# senror_input.net
KiCad netlist of a schematic drawn in Altium Designer
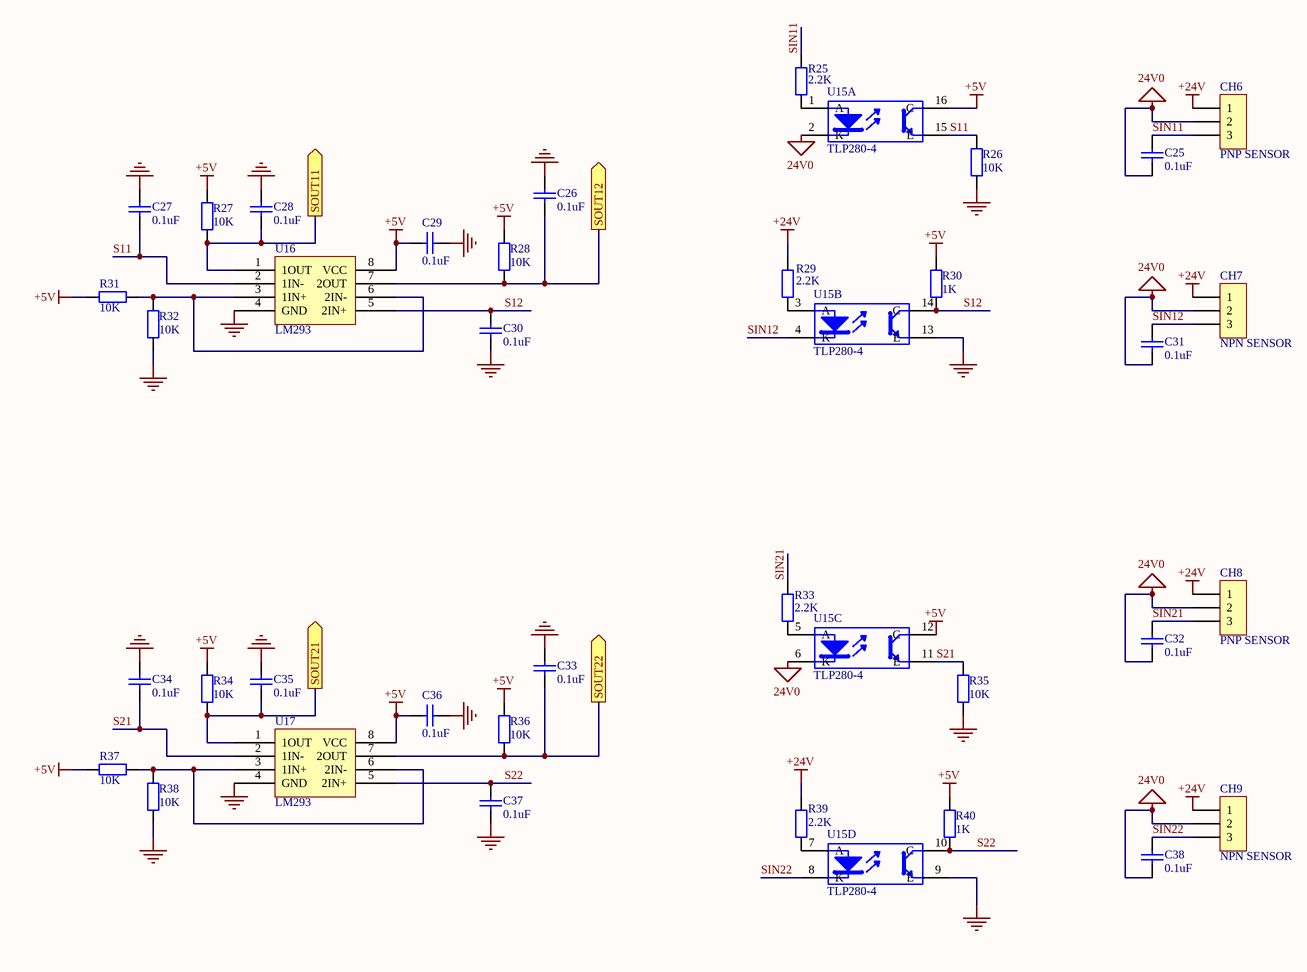
[diagram p0: senror_input.SchDoc]

(export (version "E")
  (design (tool "Eeschema 10.0.6"))
  (components
    (comp (ref "C25")
      (value "0.1uF")
      (footprint "0805")
      (description "Capacitor")
      (fields (field (name "Comment") "Cap") (field (name "PUBLISHER") "Altium Limited"))
      (libsource (lib "Miscellaneous Devices") (part "Cap"))
    )
    (comp (ref "C26")
      (value "0.1uF")
      (footprint "0805")
      (description "Capacitor")
      (fields (field (name "Comment") "Cap") (field (name "PUBLISHER") "Altium Limited"))
      (libsource (lib "Miscellaneous Devices") (part "Cap"))
    )
    (comp (ref "C27")
      (value "0.1uF")
      (footprint "0805")
      (description "Capacitor")
      (fields (field (name "Comment") "Cap") (field (name "PUBLISHER") "Altium Limited"))
      (libsource (lib "Miscellaneous Devices") (part "Cap"))
    )
    (comp (ref "C28")
      (value "0.1uF")
      (footprint "0805")
      (description "Capacitor")
      (fields (field (name "Comment") "Cap") (field (name "PUBLISHER") "Altium Limited"))
      (libsource (lib "Miscellaneous Devices") (part "Cap"))
    )
    (comp (ref "C29")
      (value "0.1uF")
      (footprint "0805")
      (description "Capacitor")
      (fields (field (name "Comment") "Cap") (field (name "PUBLISHER") "Altium Limited"))
      (libsource (lib "Miscellaneous Devices") (part "Cap"))
    )
    (comp (ref "C30")
      (value "0.1uF")
      (footprint "0805")
      (description "Capacitor")
      (fields (field (name "Comment") "Cap") (field (name "PUBLISHER") "Altium Limited"))
      (libsource (lib "Miscellaneous Devices") (part "Cap"))
    )
    (comp (ref "C31")
      (value "0.1uF")
      (footprint "0805")
      (description "Capacitor")
      (fields (field (name "Comment") "Cap") (field (name "PUBLISHER") "Altium Limited"))
      (libsource (lib "Miscellaneous Devices") (part "Cap"))
    )
    (comp (ref "C32")
      (value "0.1uF")
      (footprint "0805")
      (description "Capacitor")
      (fields (field (name "Comment") "Cap") (field (name "PUBLISHER") "Altium Limited"))
      (libsource (lib "Miscellaneous Devices") (part "Cap"))
    )
    (comp (ref "C33")
      (value "0.1uF")
      (footprint "0805")
      (description "Capacitor")
      (fields (field (name "Comment") "Cap") (field (name "PUBLISHER") "Altium Limited"))
      (libsource (lib "Miscellaneous Devices") (part "Cap"))
    )
    (comp (ref "C34")
      (value "0.1uF")
      (footprint "0805")
      (description "Capacitor")
      (fields (field (name "Comment") "Cap") (field (name "PUBLISHER") "Altium Limited"))
      (libsource (lib "Miscellaneous Devices") (part "Cap"))
    )
    (comp (ref "C35")
      (value "0.1uF")
      (footprint "0805")
      (description "Capacitor")
      (fields (field (name "Comment") "Cap") (field (name "PUBLISHER") "Altium Limited"))
      (libsource (lib "Miscellaneous Devices") (part "Cap"))
    )
    (comp (ref "C36")
      (value "0.1uF")
      (footprint "0805")
      (description "Capacitor")
      (fields (field (name "Comment") "Cap") (field (name "PUBLISHER") "Altium Limited"))
      (libsource (lib "Miscellaneous Devices") (part "Cap"))
    )
    (comp (ref "C37")
      (value "0.1uF")
      (footprint "0805")
      (description "Capacitor")
      (fields (field (name "Comment") "Cap") (field (name "PUBLISHER") "Altium Limited"))
      (libsource (lib "Miscellaneous Devices") (part "Cap"))
    )
    (comp (ref "C38")
      (value "0.1uF")
      (footprint "0805")
      (description "Capacitor")
      (fields (field (name "Comment") "Cap") (field (name "PUBLISHER") "Altium Limited"))
      (libsource (lib "Miscellaneous Devices") (part "Cap"))
    )
    (comp (ref "CH6")
      (value "HEADER1X3")
      (footprint "CH3.96-3PIN")
      (fields (field (name "ALTIUM_UNNAMED_1") "PNP SENSOR"))
      (libsource (lib "myIntegrated_Library1") (part "HEADER1X3"))
    )
    (comp (ref "CH7")
      (value "HEADER1X3")
      (footprint "CH3.96-3PIN")
      (fields (field (name "ALTIUM_UNNAMED_1") "NPN SENSOR"))
      (libsource (lib "myIntegrated_Library1") (part "HEADER1X3"))
    )
    (comp (ref "CH8")
      (value "HEADER1X3")
      (footprint "CH3.96-3PIN")
      (fields (field (name "ALTIUM_UNNAMED_1") "PNP SENSOR"))
      (libsource (lib "myIntegrated_Library1") (part "HEADER1X3"))
    )
    (comp (ref "CH9")
      (value "HEADER1X3")
      (footprint "CH3.96-3PIN")
      (fields (field (name "ALTIUM_UNNAMED_1") "NPN SENSOR"))
      (libsource (lib "myIntegrated_Library1") (part "HEADER1X3"))
    )
    (comp (ref "R25")
      (value "2.2K")
      (footprint "0805")
      (description "Resistor")
      (fields (field (name "Comment") "Res2") (field (name "PUBLISHER") "Altium Limited"))
      (libsource (lib "Miscellaneous Devices") (part "Res2"))
    )
    (comp (ref "R26")
      (value "10K")
      (footprint "0805")
      (description "Resistor")
      (fields (field (name "Comment") "Res2") (field (name "PUBLISHER") "Altium Limited"))
      (libsource (lib "Miscellaneous Devices") (part "Res2"))
    )
    (comp (ref "R27")
      (value "10K")
      (footprint "0805")
      (description "Resistor")
      (fields (field (name "Comment") "Res2") (field (name "PUBLISHER") "Altium Limited"))
      (libsource (lib "Miscellaneous Devices") (part "Res2"))
    )
    (comp (ref "R28")
      (value "10K")
      (footprint "0805")
      (description "Resistor")
      (fields (field (name "Comment") "Res2") (field (name "PUBLISHER") "Altium Limited"))
      (libsource (lib "Miscellaneous Devices") (part "Res2"))
    )
    (comp (ref "R29")
      (value "2.2K")
      (footprint "0805")
      (description "Resistor")
      (fields (field (name "Comment") "Res2") (field (name "PUBLISHER") "Altium Limited"))
      (libsource (lib "Miscellaneous Devices") (part "Res2"))
    )
    (comp (ref "R30")
      (value "1K")
      (footprint "0805")
      (description "Resistor")
      (fields (field (name "Comment") "Res2") (field (name "PUBLISHER") "Altium Limited"))
      (libsource (lib "Miscellaneous Devices") (part "Res2"))
    )
    (comp (ref "R31")
      (value "10K")
      (footprint "0805")
      (description "Resistor")
      (fields (field (name "Comment") "Res2") (field (name "PUBLISHER") "Altium Limited"))
      (libsource (lib "") (part "Res2_1"))
    )
    (comp (ref "R32")
      (value "10K")
      (footprint "0805")
      (description "Resistor")
      (fields (field (name "Comment") "Res2") (field (name "PUBLISHER") "Altium Limited"))
      (libsource (lib "Miscellaneous Devices") (part "Res2"))
    )
    (comp (ref "R33")
      (value "2.2K")
      (footprint "0805")
      (description "Resistor")
      (fields (field (name "Comment") "Res2") (field (name "PUBLISHER") "Altium Limited"))
      (libsource (lib "Miscellaneous Devices") (part "Res2"))
    )
    (comp (ref "R34")
      (value "10K")
      (footprint "0805")
      (description "Resistor")
      (fields (field (name "Comment") "Res2") (field (name "PUBLISHER") "Altium Limited"))
      (libsource (lib "Miscellaneous Devices") (part "Res2"))
    )
    (comp (ref "R35")
      (value "10K")
      (footprint "0805")
      (description "Resistor")
      (fields (field (name "Comment") "Res2") (field (name "PUBLISHER") "Altium Limited"))
      (libsource (lib "Miscellaneous Devices") (part "Res2"))
    )
    (comp (ref "R36")
      (value "10K")
      (footprint "0805")
      (description "Resistor")
      (fields (field (name "Comment") "Res2") (field (name "PUBLISHER") "Altium Limited"))
      (libsource (lib "Miscellaneous Devices") (part "Res2"))
    )
    (comp (ref "R37")
      (value "10K")
      (footprint "0805")
      (description "Resistor")
      (fields (field (name "Comment") "Res2") (field (name "PUBLISHER") "Altium Limited"))
      (libsource (lib "") (part "Res2_1"))
    )
    (comp (ref "R38")
      (value "10K")
      (footprint "0805")
      (description "Resistor")
      (fields (field (name "Comment") "Res2") (field (name "PUBLISHER") "Altium Limited"))
      (libsource (lib "Miscellaneous Devices") (part "Res2"))
    )
    (comp (ref "R39")
      (value "2.2K")
      (footprint "0805")
      (description "Resistor")
      (fields (field (name "Comment") "Res2") (field (name "PUBLISHER") "Altium Limited"))
      (libsource (lib "Miscellaneous Devices") (part "Res2"))
    )
    (comp (ref "R40")
      (value "1K")
      (footprint "0805")
      (description "Resistor")
      (fields (field (name "Comment") "Res2") (field (name "PUBLISHER") "Altium Limited"))
      (libsource (lib "Miscellaneous Devices") (part "Res2"))
    )
    (comp (ref "U15") (value "TLP280-4") (footprint "SO16") (libsource (lib "WH V20") (part "TLP521-4")))
    (comp (ref "U16")
      (value "LM293")
      (footprint "SOP8-OP27")
      (libsource (lib "myIntegrated_Library1") (part "LM293"))
    )
    (comp (ref "U17")
      (value "LM293")
      (footprint "SOP8-OP27")
      (libsource (lib "myIntegrated_Library1") (part "LM293"))
    )
  )
  (nets
    (net (code "1") (name "+5V") (class "Default")
      (node (ref "C29") (pin "2") (pinfunction "2_2") (pintype "passive"))
      (node (ref "C36") (pin "2") (pinfunction "2_2") (pintype "passive"))
      (node (ref "R27") (pin "1") (pinfunction "1_1") (pintype "passive"))
      (node (ref "R28") (pin "1") (pinfunction "1_1") (pintype "passive"))
      (node (ref "R30") (pin "1") (pinfunction "1_1") (pintype "passive"))
      (node (ref "R31") (pin "1") (pinfunction "1_1") (pintype "passive"))
      (node (ref "R34") (pin "1") (pinfunction "1_1") (pintype "passive"))
      (node (ref "R36") (pin "1") (pinfunction "1_1") (pintype "passive"))
      (node (ref "R37") (pin "1") (pinfunction "1_1") (pintype "passive"))
      (node (ref "R40") (pin "1") (pinfunction "1_1") (pintype "passive"))
      (node (ref "U15") (pin "12") (pinfunction "C_12") (pintype "passive"))
      (node (ref "U15") (pin "16") (pinfunction "C_16") (pintype "passive"))
      (node (ref "U16") (pin "8") (pinfunction "VCC_8") (pintype "passive"))
      (node (ref "U17") (pin "8") (pinfunction "VCC_8") (pintype "passive"))
    )
    (net (code "2") (name "+24V") (class "Default")
      (node (ref "CH6") (pin "1") (pinfunction "1_1") (pintype "passive"))
      (node (ref "CH7") (pin "1") (pinfunction "1_1") (pintype "passive"))
      (node (ref "CH8") (pin "1") (pinfunction "1_1") (pintype "passive"))
      (node (ref "CH9") (pin "1") (pinfunction "1_1") (pintype "passive"))
      (node (ref "R29") (pin "1") (pinfunction "1_1") (pintype "passive"))
      (node (ref "R39") (pin "1") (pinfunction "1_1") (pintype "passive"))
    )
    (net (code "3") (name "/S11") (class "Default")
      (node (ref "C27") (pin "2") (pinfunction "2_2") (pintype "passive"))
      (node (ref "R26") (pin "1") (pinfunction "1_1") (pintype "passive"))
      (node (ref "U15") (pin "15") (pinfunction "E_15") (pintype "passive"))
      (node (ref "U16") (pin "2") (pinfunction "1IN-_2") (pintype "passive"))
    )
    (net (code "4") (name "/S12") (class "Default")
      (node (ref "C30") (pin "2") (pinfunction "2_2") (pintype "passive"))
      (node (ref "R30") (pin "2") (pinfunction "2_2") (pintype "passive"))
      (node (ref "U15") (pin "14") (pinfunction "C_14") (pintype "passive"))
      (node (ref "U16") (pin "5") (pinfunction "2IN+_5") (pintype "passive"))
    )
    (net (code "5") (name "/S21") (class "Default")
      (node (ref "C34") (pin "2") (pinfunction "2_2") (pintype "passive"))
      (node (ref "R35") (pin "1") (pinfunction "1_1") (pintype "passive"))
      (node (ref "U15") (pin "11") (pinfunction "E_11") (pintype "passive"))
      (node (ref "U17") (pin "2") (pinfunction "1IN-_2") (pintype "passive"))
    )
    (net (code "6") (name "/S22") (class "Default")
      (node (ref "C37") (pin "2") (pinfunction "2_2") (pintype "passive"))
      (node (ref "R40") (pin "2") (pinfunction "2_2") (pintype "passive"))
      (node (ref "U15") (pin "10") (pinfunction "C_10") (pintype "passive"))
      (node (ref "U17") (pin "5") (pinfunction "2IN+_5") (pintype "passive"))
    )
    (net (code "7") (name "/SIN11") (class "Default")
      (node (ref "C25") (pin "1") (pinfunction "1_1") (pintype "passive"))
      (node (ref "CH6") (pin "3") (pinfunction "3_3") (pintype "passive"))
      (node (ref "R25") (pin "1") (pinfunction "1_1") (pintype "passive"))
    )
    (net (code "8") (name "/SIN12") (class "Default")
      (node (ref "C31") (pin "1") (pinfunction "1_1") (pintype "passive"))
      (node (ref "CH7") (pin "3") (pinfunction "3_3") (pintype "passive"))
      (node (ref "U15") (pin "4") (pinfunction "K_4") (pintype "passive"))
    )
    (net (code "9") (name "/SIN21") (class "Default")
      (node (ref "C32") (pin "1") (pinfunction "1_1") (pintype "passive"))
      (node (ref "CH8") (pin "3") (pinfunction "3_3") (pintype "passive"))
      (node (ref "R33") (pin "1") (pinfunction "1_1") (pintype "passive"))
    )
    (net (code "10") (name "/SIN22") (class "Default")
      (node (ref "C38") (pin "1") (pinfunction "1_1") (pintype "passive"))
      (node (ref "CH9") (pin "3") (pinfunction "3_3") (pintype "passive"))
      (node (ref "U15") (pin "8") (pinfunction "K_8") (pintype "passive"))
    )
    (net (code "11") (name "/SOUT11") (class "Default")
      (node (ref "C28") (pin "2") (pinfunction "2_2") (pintype "passive"))
      (node (ref "R27") (pin "2") (pinfunction "2_2") (pintype "passive"))
      (node (ref "U16") (pin "1") (pinfunction "1OUT_1") (pintype "passive"))
    )
    (net (code "12") (name "/SOUT12") (class "Default")
      (node (ref "C26") (pin "2") (pinfunction "2_2") (pintype "passive"))
      (node (ref "R28") (pin "2") (pinfunction "2_2") (pintype "passive"))
      (node (ref "U16") (pin "7") (pinfunction "2OUT_7") (pintype "passive"))
    )
    (net (code "13") (name "/SOUT21") (class "Default")
      (node (ref "C35") (pin "2") (pinfunction "2_2") (pintype "passive"))
      (node (ref "R34") (pin "2") (pinfunction "2_2") (pintype "passive"))
      (node (ref "U17") (pin "1") (pinfunction "1OUT_1") (pintype "passive"))
    )
    (net (code "14") (name "/SOUT22") (class "Default")
      (node (ref "C33") (pin "2") (pinfunction "2_2") (pintype "passive"))
      (node (ref "R36") (pin "2") (pinfunction "2_2") (pintype "passive"))
      (node (ref "U17") (pin "7") (pinfunction "2OUT_7") (pintype "passive"))
    )
    (net (code "15") (name "24V0") (class "Default")
      (node (ref "C25") (pin "2") (pinfunction "2_2") (pintype "passive"))
      (node (ref "C31") (pin "2") (pinfunction "2_2") (pintype "passive"))
      (node (ref "C32") (pin "2") (pinfunction "2_2") (pintype "passive"))
      (node (ref "C38") (pin "2") (pinfunction "2_2") (pintype "passive"))
      (node (ref "CH6") (pin "2") (pinfunction "2_2") (pintype "passive"))
      (node (ref "CH7") (pin "2") (pinfunction "2_2") (pintype "passive"))
      (node (ref "CH8") (pin "2") (pinfunction "2_2") (pintype "passive"))
      (node (ref "CH9") (pin "2") (pinfunction "2_2") (pintype "passive"))
      (node (ref "U15") (pin "2") (pinfunction "K_2") (pintype "passive"))
      (node (ref "U15") (pin "6") (pinfunction "K_6") (pintype "passive"))
    )
    (net (code "16") (name "GND") (class "Default")
      (node (ref "C26") (pin "1") (pinfunction "1_1") (pintype "passive"))
      (node (ref "C27") (pin "1") (pinfunction "1_1") (pintype "passive"))
      (node (ref "C28") (pin "1") (pinfunction "1_1") (pintype "passive"))
      (node (ref "C29") (pin "1") (pinfunction "1_1") (pintype "passive"))
      (node (ref "C30") (pin "1") (pinfunction "1_1") (pintype "passive"))
      (node (ref "C33") (pin "1") (pinfunction "1_1") (pintype "passive"))
      (node (ref "C34") (pin "1") (pinfunction "1_1") (pintype "passive"))
      (node (ref "C35") (pin "1") (pinfunction "1_1") (pintype "passive"))
      (node (ref "C36") (pin "1") (pinfunction "1_1") (pintype "passive"))
      (node (ref "C37") (pin "1") (pinfunction "1_1") (pintype "passive"))
      (node (ref "R26") (pin "2") (pinfunction "2_2") (pintype "passive"))
      (node (ref "R32") (pin "2") (pinfunction "2_2") (pintype "passive"))
      (node (ref "R35") (pin "2") (pinfunction "2_2") (pintype "passive"))
      (node (ref "R38") (pin "2") (pinfunction "2_2") (pintype "passive"))
      (node (ref "U15") (pin "13") (pinfunction "E_13") (pintype "passive"))
      (node (ref "U15") (pin "9") (pinfunction "E_9") (pintype "passive"))
      (node (ref "U16") (pin "4") (pinfunction "GND_4") (pintype "passive"))
      (node (ref "U17") (pin "4") (pinfunction "GND_4") (pintype "passive"))
    )
    (net (code "17") (name "Net-(U15A-A)") (class "Default")
      (node (ref "R25") (pin "2") (pinfunction "2_2") (pintype "passive"))
      (node (ref "U15") (pin "1") (pinfunction "A_1") (pintype "passive"))
    )
    (net (code "18") (name "Net-(U15B-A)") (class "Default")
      (node (ref "R29") (pin "2") (pinfunction "2_2") (pintype "passive"))
      (node (ref "U15") (pin "3") (pinfunction "A_3") (pintype "passive"))
    )
    (net (code "19") (name "Net-(U15C-A)") (class "Default")
      (node (ref "R33") (pin "2") (pinfunction "2_2") (pintype "passive"))
      (node (ref "U15") (pin "5") (pinfunction "A_5") (pintype "passive"))
    )
    (net (code "20") (name "Net-(U15D-A)") (class "Default")
      (node (ref "R39") (pin "2") (pinfunction "2_2") (pintype "passive"))
      (node (ref "U15") (pin "7") (pinfunction "A_7") (pintype "passive"))
    )
    (net (code "21") (name "Net-(U16-1IN+)") (class "Default")
      (node (ref "R31") (pin "2") (pinfunction "2_2") (pintype "passive"))
      (node (ref "R32") (pin "1") (pinfunction "1_1") (pintype "passive"))
      (node (ref "U16") (pin "3") (pinfunction "1IN+_3") (pintype "passive"))
      (node (ref "U16") (pin "6") (pinfunction "2IN-_6") (pintype "passive"))
    )
    (net (code "22") (name "Net-(U17-1IN+)") (class "Default")
      (node (ref "R37") (pin "2") (pinfunction "2_2") (pintype "passive"))
      (node (ref "R38") (pin "1") (pinfunction "1_1") (pintype "passive"))
      (node (ref "U17") (pin "3") (pinfunction "1IN+_3") (pintype "passive"))
      (node (ref "U17") (pin "6") (pinfunction "2IN-_6") (pintype "passive"))
    )
  )
)
